# adc_dac_rxd6.net
KiCad netlist of a schematic drawn in Altium Designer
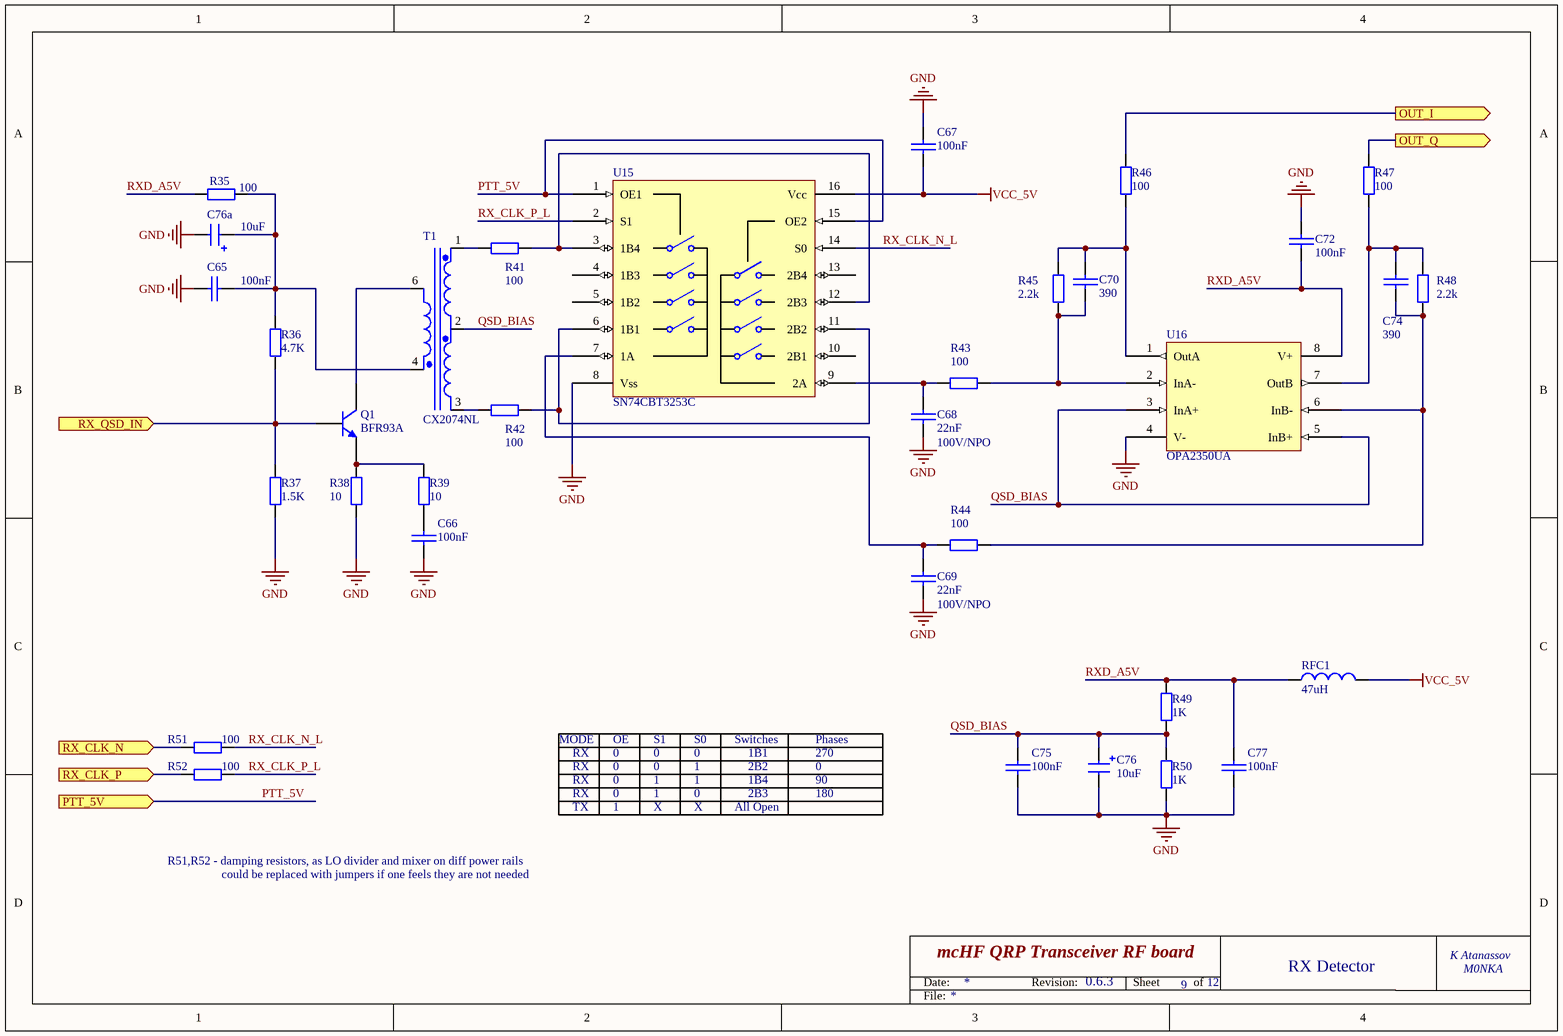
[diagram p0: adc_dac_rxd6.SchDoc]

(export (version "E")
  (design (tool "Eeschema 10.0.6"))
  (components
    (comp (ref "C65")
      (value "100nF")
      (footprint "0805-Pro")
      (description "Capacitor")
      (libsource (lib "mcHF_rf") (part "CAP"))
    )
    (comp (ref "C66")
      (value "100nF")
      (footprint "0805-Pro")
      (description "Capacitor")
      (libsource (lib "mcHF_rf") (part "CAP"))
    )
    (comp (ref "C67")
      (value "100nF")
      (footprint "0805-Pro")
      (description "Capacitor")
      (libsource (lib "mcHF_rf") (part "CAP"))
    )
    (comp (ref "C68")
      (value "22nF")
      (footprint "CAP_B")
      (description "Capacitor")
      (fields (field (name "VOLTAGE") "100V/NPO"))
      (libsource (lib "mcHF_rf") (part "CAP"))
    )
    (comp (ref "C69")
      (value "22nF")
      (footprint "CAP_B")
      (description "Capacitor")
      (fields (field (name "VOLTAGE") "100V/NPO"))
      (libsource (lib "mcHF_rf") (part "CAP"))
    )
    (comp (ref "C70")
      (value "390")
      (footprint "0805-Pro")
      (description "Capacitor")
      (libsource (lib "mcHF_rf") (part "CAP"))
    )
    (comp (ref "C72")
      (value "100nF")
      (footprint "0805-Pro")
      (description "Capacitor")
      (libsource (lib "mcHF_rf") (part "CAP"))
    )
    (comp (ref "C74")
      (value "390")
      (footprint "0805-Pro")
      (description "Capacitor")
      (libsource (lib "mcHF_rf") (part "CAP"))
    )
    (comp (ref "C75")
      (value "100nF")
      (footprint "0805-Pro")
      (description "Capacitor")
      (libsource (lib "mcHF_rf") (part "CAP"))
    )
    (comp (ref "C76")
      (value "10uF")
      (footprint "1206_Elec_Cap_N")
      (description "Electrolitic capacitor")
      (libsource (lib "mcHF_rf") (part "CAP-POL"))
    )
    (comp (ref "C76a")
      (value "10uF")
      (footprint "1206_Elec_Cap_N")
      (description "Electrolitic capacitor")
      (libsource (lib "mcHF_rf") (part "CAP-POL"))
    )
    (comp (ref "C77")
      (value "100nF")
      (footprint "0805-Pro")
      (description "Capacitor")
      (libsource (lib "mcHF_rf") (part "CAP"))
    )
    (comp (ref "Q1")
      (value "BFR93A")
      (footprint "SOT-23-Pro")
      (description "TRANSISTOR, RF, NPN, 12V, 0.035MA,SOT-23")
      (libsource (lib "mcHF_rf") (part "BFR93A"))
    )
    (comp (ref "R35")
      (value "100")
      (footprint "0805-Pro")
      (description "Resistor")
      (libsource (lib "") (part "RES_1"))
    )
    (comp (ref "R36")
      (value "4.7K")
      (footprint "0805-Pro")
      (description "Resistor")
      (libsource (lib "") (part "RES_2"))
    )
    (comp (ref "R37")
      (value "1.5K")
      (footprint "0805-Pro")
      (description "Resistor")
      (libsource (lib "") (part "RES_2"))
    )
    (comp (ref "R38")
      (value "10")
      (footprint "0805-Pro")
      (description "Resistor")
      (libsource (lib "mcHF_rf") (part "RES"))
    )
    (comp (ref "R39")
      (value "10")
      (footprint "0805-Pro")
      (description "Resistor")
      (libsource (lib "mcHF_rf") (part "RES"))
    )
    (comp (ref "R41")
      (value "100")
      (footprint "0805-Pro")
      (description "Resistor")
      (libsource (lib "") (part "RES_1"))
    )
    (comp (ref "R42")
      (value "100")
      (footprint "0805-Pro")
      (description "Resistor")
      (libsource (lib "") (part "RES_1"))
    )
    (comp (ref "R43")
      (value "100")
      (footprint "0805-Pro")
      (description "Resistor")
      (libsource (lib "") (part "RES_1"))
    )
    (comp (ref "R44")
      (value "100")
      (footprint "0805-Pro")
      (description "Resistor")
      (libsource (lib "") (part "RES_1"))
    )
    (comp (ref "R45")
      (value "2.2k")
      (footprint "0805-Pro")
      (description "Resistor")
      (libsource (lib "mcHF_rf") (part "RES"))
    )
    (comp (ref "R46")
      (value "100")
      (footprint "0805-Pro")
      (description "Resistor")
      (libsource (lib "mcHF_rf") (part "RES"))
    )
    (comp (ref "R47")
      (value "100")
      (footprint "0805-Pro")
      (description "Resistor")
      (libsource (lib "mcHF_rf") (part "RES"))
    )
    (comp (ref "R48")
      (value "2.2k")
      (footprint "0805-Pro")
      (description "Resistor")
      (libsource (lib "mcHF_rf") (part "RES"))
    )
    (comp (ref "R49")
      (value "1K")
      (footprint "0805-Pro")
      (description "Resistor")
      (libsource (lib "mcHF_rf") (part "RES"))
    )
    (comp (ref "R50")
      (value "1K")
      (footprint "0805-Pro")
      (description "Resistor")
      (libsource (lib "mcHF_rf") (part "RES"))
    )
    (comp (ref "R51")
      (value "100")
      (footprint "0805-Pro")
      (description "Resistor")
      (libsource (lib "") (part "RES_3"))
    )
    (comp (ref "R52")
      (value "100")
      (footprint "0805-Pro")
      (description "Resistor")
      (libsource (lib "") (part "RES_3"))
    )
    (comp (ref "RFC1")
      (value "47uH")
      (footprint "0805-Pro")
      (description "INDUCTOR, SIGNAL LINE, 4.7UH, 1005")
      (libsource (lib "mcHF_rf") (part "TDK-NLV25T"))
    )
    (comp (ref "T1")
      (value "CX2074NL")
      (footprint "SOP5_NEW1")
      (description "Wideband RF Transformer 1:4")
      (libsource (lib "mcHF_rf") (part "CX2074NL"))
    )
    (comp (ref "U15")
      (value "SN74CBT3253C")
      (footprint "SO-16-Pro")
      (description "Dual 4:1 Demux/Analog Switch")
      (libsource (lib "mcHF_rf") (part "SN74CBT3253C"))
    )
    (comp (ref "U16")
      (value "OPA2350UA")
      (footprint "SO-8-Pro")
      (description "High Speed, Single Supply OpAmp")
      (libsource (lib "mcHF_rf") (part "OPA2350UA"))
    )
  )
  (nets
    (net (code "1") (name "/OUT_I") (class "Default")
      (node (ref "R46") (pin "2") (pinfunction "2_2") (pintype "passive"))
    )
    (net (code "2") (name "/OUT_Q") (class "Default")
      (node (ref "R47") (pin "2") (pinfunction "2_2") (pintype "passive"))
    )
    (net (code "3") (name "/PTT_5V") (class "Default")
      (node (ref "U15") (pin "1") (pinfunction "OE1_1") (pintype "input"))
      (node (ref "U15") (pin "15") (pinfunction "OE2_15") (pintype "input"))
    )
    (net (code "4") (name "/QSD_BIAS") (class "Default")
      (node (ref "C75") (pin "2") (pinfunction "2_2") (pintype "passive"))
      (node (ref "C76") (pin "1") (pinfunction "1_1") (pintype "passive"))
      (node (ref "R49") (pin "1") (pinfunction "1_1") (pintype "passive"))
      (node (ref "R50") (pin "2") (pinfunction "2_2") (pintype "passive"))
      (node (ref "T1") (pin "2") (pinfunction "SecCmn_2") (pintype "passive"))
      (node (ref "U16") (pin "3") (pinfunction "InA+_3") (pintype "input"))
      (node (ref "U16") (pin "5") (pinfunction "InB+_5") (pintype "input"))
    )
    (net (code "5") (name "/RXD_A5V") (class "Default")
      (node (ref "C72") (pin "2") (pinfunction "2_2") (pintype "passive"))
      (node (ref "C77") (pin "2") (pinfunction "2_2") (pintype "passive"))
      (node (ref "R35") (pin "1") (pinfunction "1_1") (pintype "passive"))
      (node (ref "R49") (pin "2") (pinfunction "2_2") (pintype "passive"))
      (node (ref "RFC1") (pin "1") (pinfunction "1_1") (pintype "passive"))
      (node (ref "U16") (pin "8") (pinfunction "V+_8") (pintype "power_in"))
    )
    (net (code "6") (name "/RX_CLK_N") (class "Default")
      (node (ref "R51") (pin "2") (pinfunction "2_2") (pintype "passive"))
    )
    (net (code "7") (name "/RX_CLK_N_L") (class "Default")
      (node (ref "R51") (pin "1") (pinfunction "1_1") (pintype "passive"))
      (node (ref "U15") (pin "14") (pinfunction "S0_14") (pintype "input"))
    )
    (net (code "8") (name "/RX_CLK_P") (class "Default")
      (node (ref "R52") (pin "2") (pinfunction "2_2") (pintype "passive"))
    )
    (net (code "9") (name "/RX_CLK_P_L") (class "Default")
      (node (ref "R52") (pin "1") (pinfunction "1_1") (pintype "passive"))
      (node (ref "U15") (pin "2") (pinfunction "S1_2") (pintype "input"))
    )
    (net (code "10") (name "/RX_QSD_IN") (class "Default")
      (node (ref "Q1") (pin "1") (pinfunction "B_1") (pintype "passive"))
      (node (ref "R36") (pin "2") (pinfunction "2_2") (pintype "passive"))
      (node (ref "R37") (pin "1") (pinfunction "1_1") (pintype "passive"))
    )
    (net (code "11") (name "GND") (class "Default")
      (node (ref "C65") (pin "2") (pinfunction "2_2") (pintype "passive"))
      (node (ref "C66") (pin "1") (pinfunction "1_1") (pintype "passive"))
      (node (ref "C67") (pin "2") (pinfunction "2_2") (pintype "passive"))
      (node (ref "C68") (pin "2") (pinfunction "2_2") (pintype "passive"))
      (node (ref "C69") (pin "2") (pinfunction "2_2") (pintype "passive"))
      (node (ref "C72") (pin "1") (pinfunction "1_1") (pintype "passive"))
      (node (ref "C75") (pin "1") (pinfunction "1_1") (pintype "passive"))
      (node (ref "C76") (pin "2") (pinfunction "2_2") (pintype "passive"))
      (node (ref "C76a") (pin "2") (pinfunction "2_2") (pintype "passive"))
      (node (ref "C77") (pin "1") (pinfunction "1_1") (pintype "passive"))
      (node (ref "R37") (pin "2") (pinfunction "2_2") (pintype "passive"))
      (node (ref "R38") (pin "1") (pinfunction "1_1") (pintype "passive"))
      (node (ref "R50") (pin "1") (pinfunction "1_1") (pintype "passive"))
      (node (ref "U15") (pin "8") (pinfunction "Vss_8") (pintype "power_in"))
      (node (ref "U16") (pin "4") (pinfunction "V-_4") (pintype "power_in"))
    )
    (net (code "12") (name "Net-(C66-Pad2)") (class "Default")
      (node (ref "C66") (pin "2") (pinfunction "2_2") (pintype "passive"))
      (node (ref "R39") (pin "1") (pinfunction "1_1") (pintype "passive"))
    )
    (net (code "13") (name "Net-(Q1-C)") (class "Default")
      (node (ref "Q1") (pin "3") (pinfunction "C_3") (pintype "passive"))
      (node (ref "T1") (pin "6") (pinfunction "Pri+_6") (pintype "passive"))
    )
    (net (code "14") (name "Net-(Q1-E)") (class "Default")
      (node (ref "Q1") (pin "2") (pinfunction "E_2") (pintype "passive"))
      (node (ref "R38") (pin "2") (pinfunction "2_2") (pintype "passive"))
      (node (ref "R39") (pin "2") (pinfunction "2_2") (pintype "passive"))
    )
    (net (code "15") (name "Net-(T1-Pri-)") (class "Default")
      (node (ref "C65") (pin "1") (pinfunction "1_1") (pintype "passive"))
      (node (ref "C76a") (pin "1") (pinfunction "1_1") (pintype "passive"))
      (node (ref "R35") (pin "2") (pinfunction "2_2") (pintype "passive"))
      (node (ref "R36") (pin "1") (pinfunction "1_1") (pintype "passive"))
      (node (ref "T1") (pin "4") (pinfunction "Pri-_4") (pintype "passive"))
    )
    (net (code "16") (name "Net-(T1-Sec0)") (class "Default")
      (node (ref "R41") (pin "1") (pinfunction "1_1") (pintype "passive"))
      (node (ref "T1") (pin "1") (pinfunction "Sec0_1") (pintype "passive"))
    )
    (net (code "17") (name "Net-(T1-Sec180)") (class "Default")
      (node (ref "R42") (pin "1") (pinfunction "1_1") (pintype "passive"))
      (node (ref "T1") (pin "3") (pinfunction "Sec180_3") (pintype "passive"))
    )
    (net (code "18") (name "Net-(U15-1A)") (class "Default")
      (node (ref "C69") (pin "1") (pinfunction "1_1") (pintype "passive"))
      (node (ref "R44") (pin "1") (pinfunction "1_1") (pintype "passive"))
      (node (ref "U15") (pin "7") (pinfunction "1A_7") (pintype "bidirectional"))
    )
    (net (code "19") (name "Net-(U15-1B1)") (class "Default")
      (node (ref "R42") (pin "2") (pinfunction "2_2") (pintype "passive"))
      (node (ref "U15") (pin "11") (pinfunction "2B2_11") (pintype "bidirectional"))
      (node (ref "U15") (pin "6") (pinfunction "1B1_6") (pintype "bidirectional"))
    )
    (net (code "20") (name "Net-(U15-1B4)") (class "Default")
      (node (ref "R41") (pin "2") (pinfunction "2_2") (pintype "passive"))
      (node (ref "U15") (pin "12") (pinfunction "2B3_12") (pintype "bidirectional"))
      (node (ref "U15") (pin "3") (pinfunction "1B4_3") (pintype "bidirectional"))
    )
    (net (code "21") (name "Net-(U15-2A)") (class "Default")
      (node (ref "C68") (pin "1") (pinfunction "1_1") (pintype "passive"))
      (node (ref "R43") (pin "1") (pinfunction "1_1") (pintype "passive"))
      (node (ref "U15") (pin "9") (pinfunction "2A_9") (pintype "bidirectional"))
    )
    (net (code "22") (name "Net-(U16-InA-)") (class "Default")
      (node (ref "C70") (pin "1") (pinfunction "1_1") (pintype "passive"))
      (node (ref "R43") (pin "2") (pinfunction "2_2") (pintype "passive"))
      (node (ref "R45") (pin "1") (pinfunction "1_1") (pintype "passive"))
      (node (ref "U16") (pin "2") (pinfunction "InA-_2") (pintype "input"))
    )
    (net (code "23") (name "Net-(U16-InB-)") (class "Default")
      (node (ref "C74") (pin "1") (pinfunction "1_1") (pintype "passive"))
      (node (ref "R44") (pin "2") (pinfunction "2_2") (pintype "passive"))
      (node (ref "R48") (pin "1") (pinfunction "1_1") (pintype "passive"))
      (node (ref "U16") (pin "6") (pinfunction "InB-_6") (pintype "input"))
    )
    (net (code "24") (name "Net-(U16-OutA)") (class "Default")
      (node (ref "C70") (pin "2") (pinfunction "2_2") (pintype "passive"))
      (node (ref "R45") (pin "2") (pinfunction "2_2") (pintype "passive"))
      (node (ref "R46") (pin "1") (pinfunction "1_1") (pintype "passive"))
      (node (ref "U16") (pin "1") (pinfunction "OutA_1") (pintype "output"))
    )
    (net (code "25") (name "Net-(U16-OutB)") (class "Default")
      (node (ref "C74") (pin "2") (pinfunction "2_2") (pintype "passive"))
      (node (ref "R47") (pin "1") (pinfunction "1_1") (pintype "passive"))
      (node (ref "R48") (pin "2") (pinfunction "2_2") (pintype "passive"))
      (node (ref "U16") (pin "7") (pinfunction "OutB_7") (pintype "output"))
    )
    (net (code "26") (name "VCC_5V") (class "Default")
      (node (ref "C67") (pin "1") (pinfunction "1_1") (pintype "passive"))
      (node (ref "RFC1") (pin "2") (pinfunction "2_2") (pintype "passive"))
      (node (ref "U15") (pin "16") (pinfunction "Vcc_16") (pintype "power_in"))
    )
    (net (code "27") (name "unconnected-(U15-1B2-Pad5)") (class "Default")
      (node (ref "U15") (pin "5") (pinfunction "1B2_5") (pintype "bidirectional"))
    )
    (net (code "28") (name "unconnected-(U15-1B3-Pad4)") (class "Default")
      (node (ref "U15") (pin "4") (pinfunction "1B3_4") (pintype "bidirectional"))
    )
    (net (code "29") (name "unconnected-(U15-2B1-Pad10)") (class "Default")
      (node (ref "U15") (pin "10") (pinfunction "2B1_10") (pintype "bidirectional"))
    )
    (net (code "30") (name "unconnected-(U15-2B4-Pad13)") (class "Default")
      (node (ref "U15") (pin "13") (pinfunction "2B4_13") (pintype "bidirectional"))
    )
  )
)
